# seedrum_mosfet_v1.net
KiCad netlist of a schematic drawn in EasyEDA
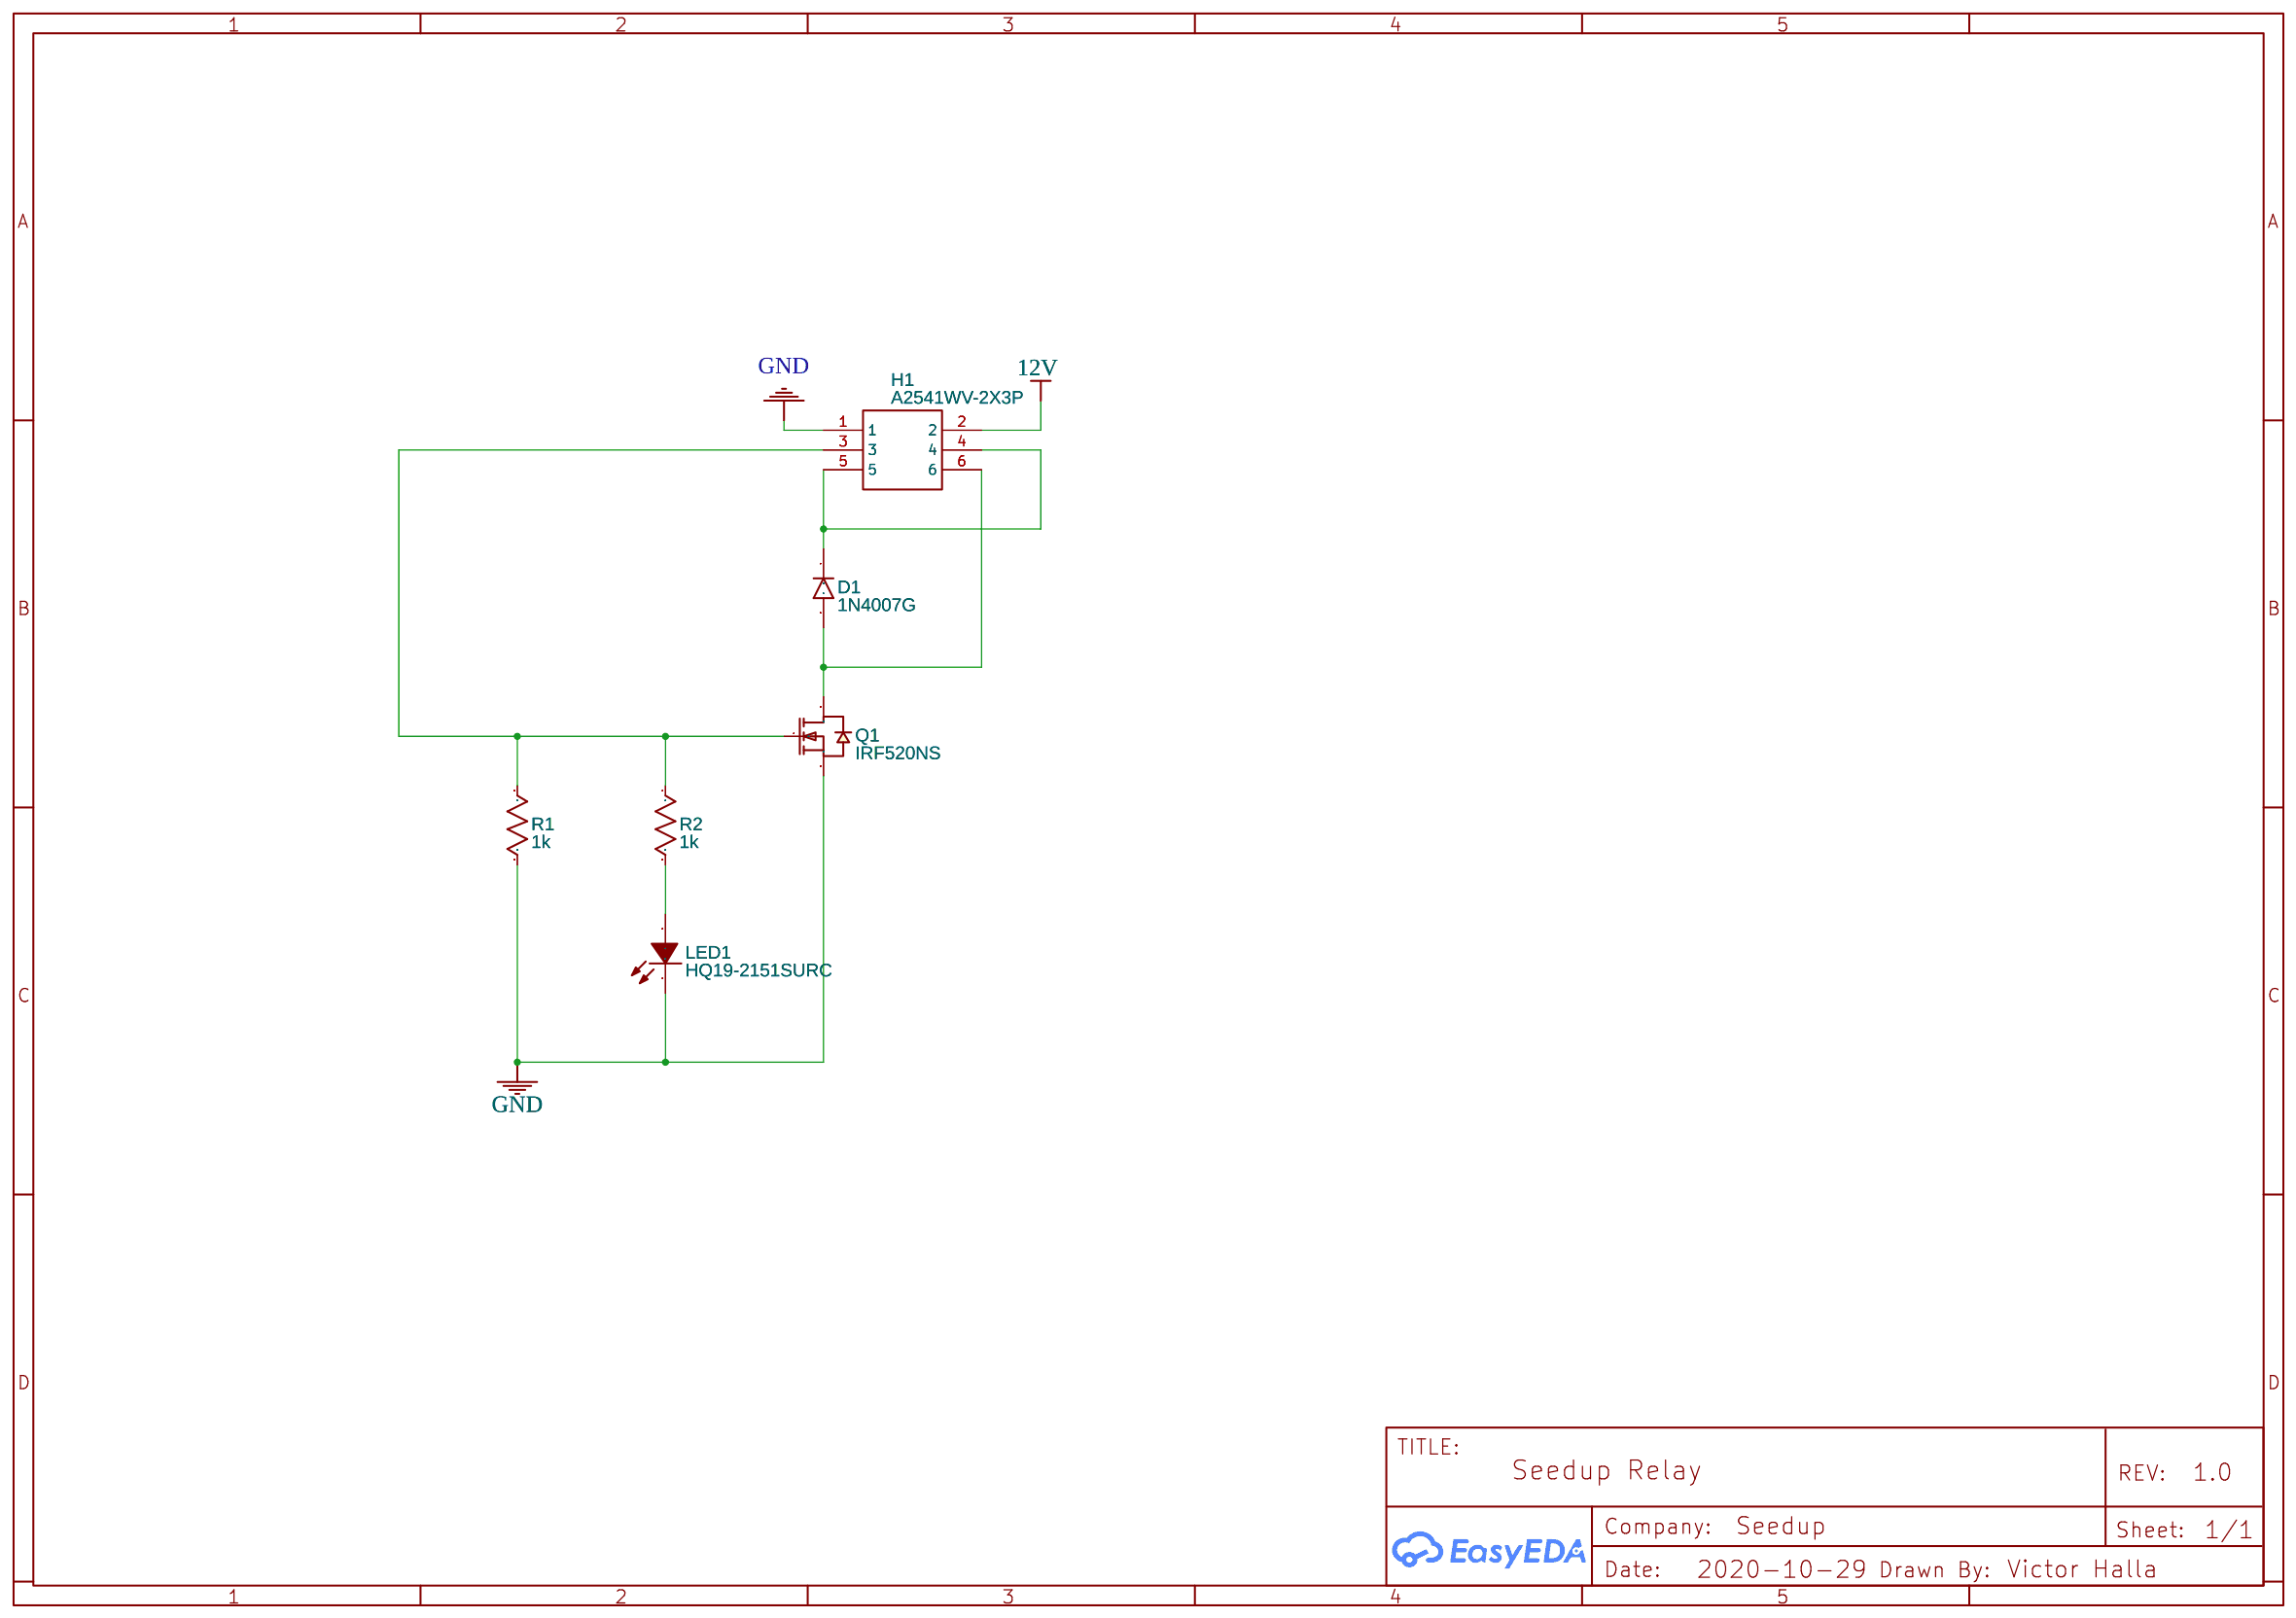
[diagram p0: schematic sheet]

(export (version "E")
  (design (tool "Eeschema 10.0.6"))
  (components
    (comp (ref "D1")
      (value "1N4007G")
      (fields (field (name "BOM_Supplier Part") "C111122"))
      (libsource (lib "") (part "1N4007G"))
    )
    (comp (ref "H1")
      (value "A2541WV-2X3P")
      (fields
        (field (name "BOM_Manufacturer Part") "A2541WV-2x3P")
        (field (name "BOM_Supplier Part") "C225518")
      )
      (libsource (lib "") (part "A2541WV-2X3P"))
    )
    (comp (ref "LED1")
      (value "HQ19-2151SURC")
      (fields (field (name "BOM_Supplier Part") "C258842"))
      (libsource (lib "") (part "HQ19-2151SURC"))
    )
    (comp (ref "Q1")
      (value "IRF520NS")
      (fields (field (name "BOM_Supplier Part") "C725067"))
      (libsource (lib "") (part "IRF520NS"))
    )
    (comp (ref "R1") (value "1k") (libsource (lib "") (part "R_0603_US")))
    (comp (ref "R2") (value "1k") (libsource (lib "") (part "R_0603_US")))
  )
  (nets
    (net (code "1") (name "12V") (class "Default")
      (node (ref "H1") (pin "2") (pinfunction "2_2") (pintype "unspecified"))
    )
    (net (code "2") (name "GND") (class "Default")
      (node (ref "H1") (pin "1") (pinfunction "1_1") (pintype "unspecified"))
      (node (ref "LED1") (pin "1") (pinfunction "K_1") (pintype "unspecified"))
      (node (ref "Q1") (pin "3") (pinfunction "S_3") (pintype "unspecified"))
      (node (ref "R1") (pin "2") (pinfunction "2_2") (pintype "unspecified"))
    )
    (net (code "3") (name "Net-(D1-A)") (class "Default")
      (node (ref "D1") (pin "2") (pinfunction "A_2") (pintype "unspecified"))
      (node (ref "H1") (pin "6") (pinfunction "6_6") (pintype "unspecified"))
      (node (ref "Q1") (pin "2") (pinfunction "D_2") (pintype "unspecified"))
    )
    (net (code "4") (name "Net-(D1-C)") (class "Default")
      (node (ref "D1") (pin "1") (pinfunction "C_1") (pintype "unspecified"))
      (node (ref "H1") (pin "4") (pinfunction "4_4") (pintype "unspecified"))
      (node (ref "H1") (pin "5") (pinfunction "5_5") (pintype "unspecified"))
    )
    (net (code "5") (name "Net-(LED1-A)") (class "Default")
      (node (ref "LED1") (pin "2") (pinfunction "A_2") (pintype "unspecified"))
      (node (ref "R2") (pin "2") (pinfunction "2_2") (pintype "unspecified"))
    )
    (net (code "6") (name "Net-(Q1-G)") (class "Default")
      (node (ref "H1") (pin "3") (pinfunction "3_3") (pintype "unspecified"))
      (node (ref "Q1") (pin "1") (pinfunction "G_1") (pintype "unspecified"))
      (node (ref "R1") (pin "1") (pinfunction "1_1") (pintype "unspecified"))
      (node (ref "R2") (pin "1") (pinfunction "1_1") (pintype "unspecified"))
    )
  )
)
